# SF_driver.net
KiCad netlist of a schematic drawn in Altium Designer
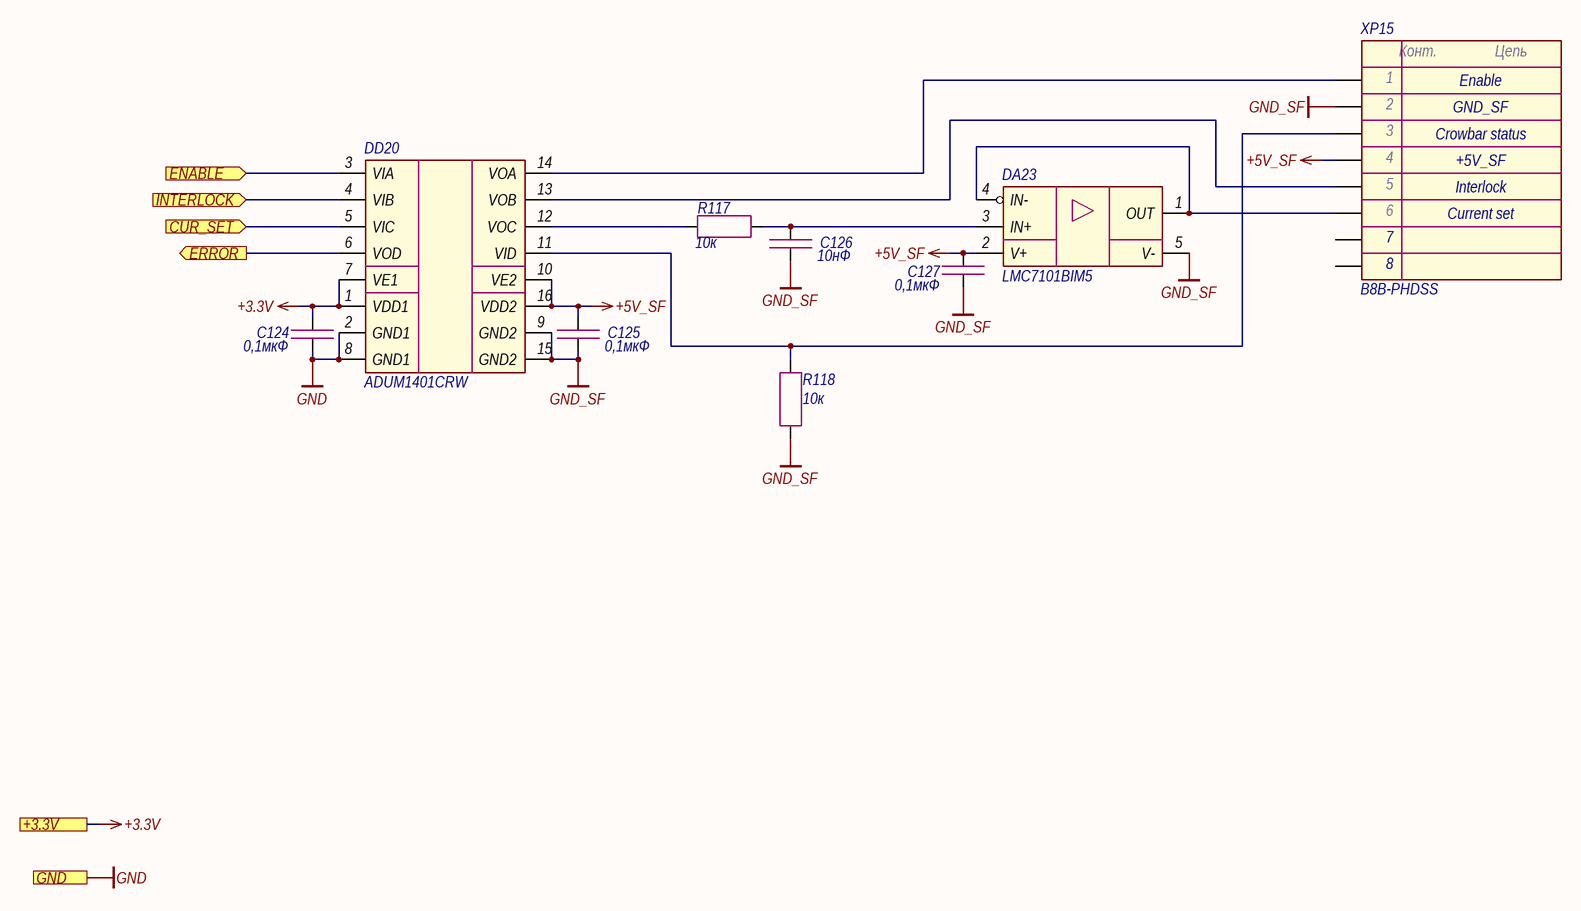
[diagram p0: SF_driver.SchDoc]

(export (version "E")
  (design (tool "Eeschema 10.0.6"))
  (components
    (comp (ref "C124")
      (value "0,1мкФ")
      (footprint "Pcb_library:CAP_0603")
      (fields (field (name "MANUFACTURER") "Murata"))
      (libsource (lib "Schem_library") (part "Capacitor"))
    )
    (comp (ref "C125")
      (value "0,1мкФ")
      (footprint "Pcb_library:CAP_0603")
      (fields (field (name "MANUFACTURER") "Murata"))
      (libsource (lib "Schem_library") (part "Capacitor"))
    )
    (comp (ref "C126")
      (value "10нФ")
      (footprint "Pcb_library:CAP_0603")
      (fields (field (name "MANUFACTURER") "Murata"))
      (libsource (lib "Schem_library") (part "Capacitor"))
    )
    (comp (ref "C127")
      (value "0,1мкФ")
      (footprint "Pcb_library:CAP_0603")
      (fields (field (name "MANUFACTURER") "Murata"))
      (libsource (lib "Schem_library") (part "Capacitor"))
    )
    (comp (ref "DA23")
      (value "LMC7101BIM5")
      (footprint "Pcb_library:SOT-23-5")
      (fields (field (name "MANUFACTURER") "Texas Instruments"))
      (libsource (lib "Schem_library") (part "LMC7101"))
    )
    (comp (ref "DD20")
      (value "ADUM1401CRW")
      (footprint "Pcb_library:SOIC-16W")
      (fields (field (name "MANUFACTURER") "Analog Devices"))
      (libsource (lib "Schem_library") (part "ADUM1401"))
    )
    (comp (ref "R117")
      (value "10к")
      (footprint "Pcb_library:RES_0603")
      (fields (field (name "MANUFACTURER") "Yageo"))
      (libsource (lib "Schem_library") (part "Resistor"))
    )
    (comp (ref "R118")
      (value "10к")
      (footprint "Pcb_library:RES_0603")
      (fields (field (name "MANUFACTURER") "Yageo"))
      (libsource (lib "Schem_library") (part "Resistor"))
    )
    (comp (ref "XP15")
      (value "B8B-PHDSS")
      (footprint "Pcb_library:B8B-PHDSS")
      (fields (field (name "MANUFACTURER") "JST"))
      (libsource (lib "Schem_library") (part "Connector-8"))
    )
  )
  (nets
    (net (code "1") (name "+3.3V") (class "Default")
      (node (ref "C124") (pin "1") (pinfunction "1_1") (pintype "passive"))
      (node (ref "DD20") (pin "1") (pinfunction "VDD1_1") (pintype "passive"))
      (node (ref "DD20") (pin "7") (pinfunction "VE1_7") (pintype "passive"))
    )
    (net (code "2") (name "+5V_SF") (class "Default")
      (node (ref "C125") (pin "1") (pinfunction "1_1") (pintype "passive"))
      (node (ref "C127") (pin "1") (pinfunction "1_1") (pintype "passive"))
      (node (ref "DA23") (pin "2") (pinfunction "V+_2") (pintype "passive"))
      (node (ref "DD20") (pin "10") (pinfunction "VE2_10") (pintype "passive"))
      (node (ref "DD20") (pin "16") (pinfunction "VDD2_16") (pintype "passive"))
      (node (ref "XP15") (pin "4") (pintype "passive"))
    )
    (net (code "3") (name "/CUR_SET") (class "Default")
      (node (ref "DD20") (pin "5") (pinfunction "VIC_5") (pintype "passive"))
    )
    (net (code "4") (name "/ENABLE") (class "Default")
      (node (ref "DD20") (pin "3") (pinfunction "VIA_3") (pintype "passive"))
    )
    (net (code "5") (name "/ERROR") (class "Default")
      (node (ref "DD20") (pin "6") (pinfunction "VOD_6") (pintype "passive"))
    )
    (net (code "6") (name "/INTERLOCK") (class "Default")
      (node (ref "DD20") (pin "4") (pinfunction "VIB_4") (pintype "passive"))
    )
    (net (code "7") (name "GND") (class "Default")
      (node (ref "C124") (pin "2") (pinfunction "2_2") (pintype "passive"))
      (node (ref "DD20") (pin "2") (pinfunction "GND1_2") (pintype "passive"))
      (node (ref "DD20") (pin "8") (pinfunction "GND1_8") (pintype "passive"))
    )
    (net (code "8") (name "GND_SF") (class "Default")
      (node (ref "C125") (pin "2") (pinfunction "2_2") (pintype "passive"))
      (node (ref "C126") (pin "2") (pinfunction "2_2") (pintype "passive"))
      (node (ref "C127") (pin "2") (pinfunction "2_2") (pintype "passive"))
      (node (ref "DA23") (pin "5") (pinfunction "V-_5") (pintype "passive"))
      (node (ref "DD20") (pin "15") (pinfunction "GND2_15") (pintype "passive"))
      (node (ref "DD20") (pin "9") (pinfunction "GND2_9") (pintype "passive"))
      (node (ref "R118") (pin "1") (pinfunction "1_1") (pintype "passive"))
      (node (ref "XP15") (pin "2") (pintype "passive"))
    )
    (net (code "9") (name "Net-(DA23-IN+)") (class "Default")
      (node (ref "C126") (pin "1") (pinfunction "1_1") (pintype "passive"))
      (node (ref "DA23") (pin "3") (pinfunction "IN+_3") (pintype "passive"))
      (node (ref "R117") (pin "2") (pinfunction "2_2") (pintype "passive"))
    )
    (net (code "10") (name "Net-(DA23-IN-)") (class "Default")
      (node (ref "DA23") (pin "1") (pinfunction "OUT_1") (pintype "passive"))
      (node (ref "DA23") (pin "4") (pinfunction "IN-_4") (pintype "passive"))
      (node (ref "XP15") (pin "6") (pintype "passive"))
    )
    (net (code "11") (name "Net-(DD20-VID)") (class "Default")
      (node (ref "DD20") (pin "11") (pinfunction "VID_11") (pintype "passive"))
      (node (ref "R118") (pin "2") (pinfunction "2_2") (pintype "passive"))
      (node (ref "XP15") (pin "3") (pintype "passive"))
    )
    (net (code "12") (name "Net-(DD20-VOA)") (class "Default")
      (node (ref "DD20") (pin "14") (pinfunction "VOA_14") (pintype "passive"))
      (node (ref "XP15") (pin "1") (pintype "passive"))
    )
    (net (code "13") (name "Net-(DD20-VOB)") (class "Default")
      (node (ref "DD20") (pin "13") (pinfunction "VOB_13") (pintype "passive"))
      (node (ref "XP15") (pin "5") (pintype "passive"))
    )
    (net (code "14") (name "Net-(DD20-VOC)") (class "Default")
      (node (ref "DD20") (pin "12") (pinfunction "VOC_12") (pintype "passive"))
      (node (ref "R117") (pin "1") (pinfunction "1_1") (pintype "passive"))
    )
    (net (code "15") (name "unconnected-(XP15-Pad7)") (class "Default")
      (node (ref "XP15") (pin "7") (pintype "passive"))
    )
    (net (code "16") (name "unconnected-(XP15-Pad8)") (class "Default")
      (node (ref "XP15") (pin "8") (pintype "passive"))
    )
  )
)
